# Volt_Meas.net
KiCad netlist of a schematic drawn in Altium Designer
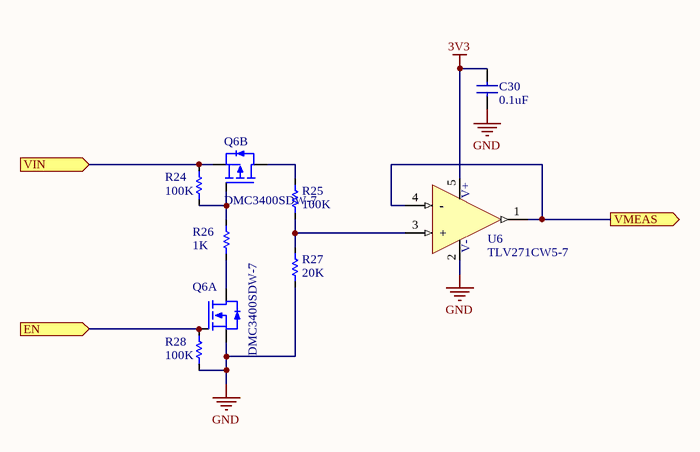
[diagram p0: Volt_Meas.SchDoc]

(export (version "E")
  (design (tool "Eeschema 10.0.6"))
  (components
    (comp (ref "C30")
      (value "0.1uF")
      (footprint "0603_CAPACITOR")
      (description "CAP CERM 0.1uF 10% 50V 0603")
      (fields
        (field (name "VOLTAGE") "50V")
        (field (name "Comment") "CAP 0.1uF 50V X7R")
        (field (name "SVP CREATOR") "Spencer Berglund")
      )
      (libsource (lib "capacitor") (part "C_0603_0.1uF_50V_10%"))
    )
    (comp (ref "Q6")
      (value "DMC3400SDW-7")
      (footprint "SOT23-6")
      (description "Mosfet Array N and P-Channel 30V 650mA, 450mA 310mW Surface Mount SOT-363")
      (fields (field (name "MANUFACTURER") "Diodes"))
      (libsource (lib "transistor") (part "Q_DMC3400SDW"))
    )
    (comp (ref "R24")
      (value "100K")
      (footprint "0603_Resistor")
      (description "Generic 0603 Resistor")
      (fields (field (name "TOLERANCE") "±1%") (field (name "MANUFACTURER") "Yageo"))
      (libsource (lib "resistor") (part "R_0603_generic_1%"))
    )
    (comp (ref "R25")
      (value "100K")
      (footprint "0603_Resistor")
      (description "Generic 0603 Resistor")
      (fields (field (name "TOLERANCE") "±1%") (field (name "MANUFACTURER") "Yageo"))
      (libsource (lib "resistor") (part "R_0603_generic_1%"))
    )
    (comp (ref "R26")
      (value "1K")
      (footprint "0603_Resistor")
      (description "Generic 0603 Resistor")
      (fields (field (name "TOLERANCE") "±1%") (field (name "MANUFACTURER") "Yageo"))
      (libsource (lib "resistor") (part "R_0603_generic_1%"))
    )
    (comp (ref "R27")
      (value "20K")
      (footprint "0603_Resistor")
      (description "Generic 0603 Resistor")
      (fields (field (name "TOLERANCE") "±1%") (field (name "MANUFACTURER") "Yageo"))
      (libsource (lib "resistor") (part "R_0603_generic_1%"))
    )
    (comp (ref "R28")
      (value "100K")
      (footprint "0603_Resistor")
      (description "Generic 0603 Resistor")
      (fields (field (name "TOLERANCE") "±1%") (field (name "MANUFACTURER") "Yageo"))
      (libsource (lib "resistor") (part "R_0603_generic_1%"))
    )
    (comp (ref "U6")
      (value "TLV271CW5-7")
      (footprint "SOT23-5")
      (description "CMOS Amplifier 1 Circuit Rail-to-Rail SOT-25")
      (fields (field (name "MANUFACTURER") "Diodes"))
      (libsource (lib "ic") (part "U_TLV27"))
    )
  )
  (nets
    (net (code "1") (name "/EN") (class "Default")
      (node (ref "Q6") (pin "2") (pinfunction "GATE_2") (pintype "passive"))
      (node (ref "R28") (pin "2") (pinfunction "2_2") (pintype "passive"))
    )
    (net (code "2") (name "/VIN") (class "Default")
      (node (ref "Q6") (pin "4") (pinfunction "SOURCE_4") (pintype "passive"))
      (node (ref "R24") (pin "2") (pinfunction "2_2") (pintype "passive"))
    )
    (net (code "3") (name "/VMEAS") (class "Default")
      (node (ref "U6") (pin "1") (pinfunction "OUT_1") (pintype "output"))
      (node (ref "U6") (pin "4") (pinfunction "-_4") (pintype "input"))
    )
    (net (code "4") (name "3V3") (class "Default")
      (node (ref "C30") (pin "1") (pinfunction "1_1") (pintype "passive"))
      (node (ref "U6") (pin "5") (pinfunction "VDD_5") (pintype "power_in"))
    )
    (net (code "5") (name "GND") (class "Default")
      (node (ref "C30") (pin "2") (pinfunction "2_2") (pintype "passive"))
      (node (ref "Q6") (pin "1") (pinfunction "SOURCE_1") (pintype "passive"))
      (node (ref "R27") (pin "1") (pinfunction "1_1") (pintype "passive"))
      (node (ref "R28") (pin "1") (pinfunction "1_1") (pintype "passive"))
      (node (ref "U6") (pin "2") (pinfunction "GND_2") (pintype "power_in"))
    )
    (net (code "6") (name "Net-(Q6A-DRAIN)") (class "Default")
      (node (ref "Q6") (pin "3") (pinfunction "DRAIN_3") (pintype "passive"))
      (node (ref "R26") (pin "1") (pinfunction "1_1") (pintype "passive"))
    )
    (net (code "7") (name "Net-(Q6B-DRAIN)") (class "Default")
      (node (ref "Q6") (pin "6") (pinfunction "DRAIN_6") (pintype "passive"))
      (node (ref "R25") (pin "2") (pinfunction "2_2") (pintype "passive"))
    )
    (net (code "8") (name "Net-(Q6B-GATE)") (class "Default")
      (node (ref "Q6") (pin "5") (pinfunction "GATE_5") (pintype "passive"))
      (node (ref "R24") (pin "1") (pinfunction "1_1") (pintype "passive"))
      (node (ref "R26") (pin "2") (pinfunction "2_2") (pintype "passive"))
    )
    (net (code "9") (name "Net-(U6-+)") (class "Default")
      (node (ref "R25") (pin "1") (pinfunction "1_1") (pintype "passive"))
      (node (ref "R27") (pin "2") (pinfunction "2_2") (pintype "passive"))
      (node (ref "U6") (pin "3") (pinfunction "+_3") (pintype "input"))
    )
  )
)
